# ProDoc_Schematic1_2026-01-19.net
KiCad netlist of a schematic drawn in EasyEDA Pro
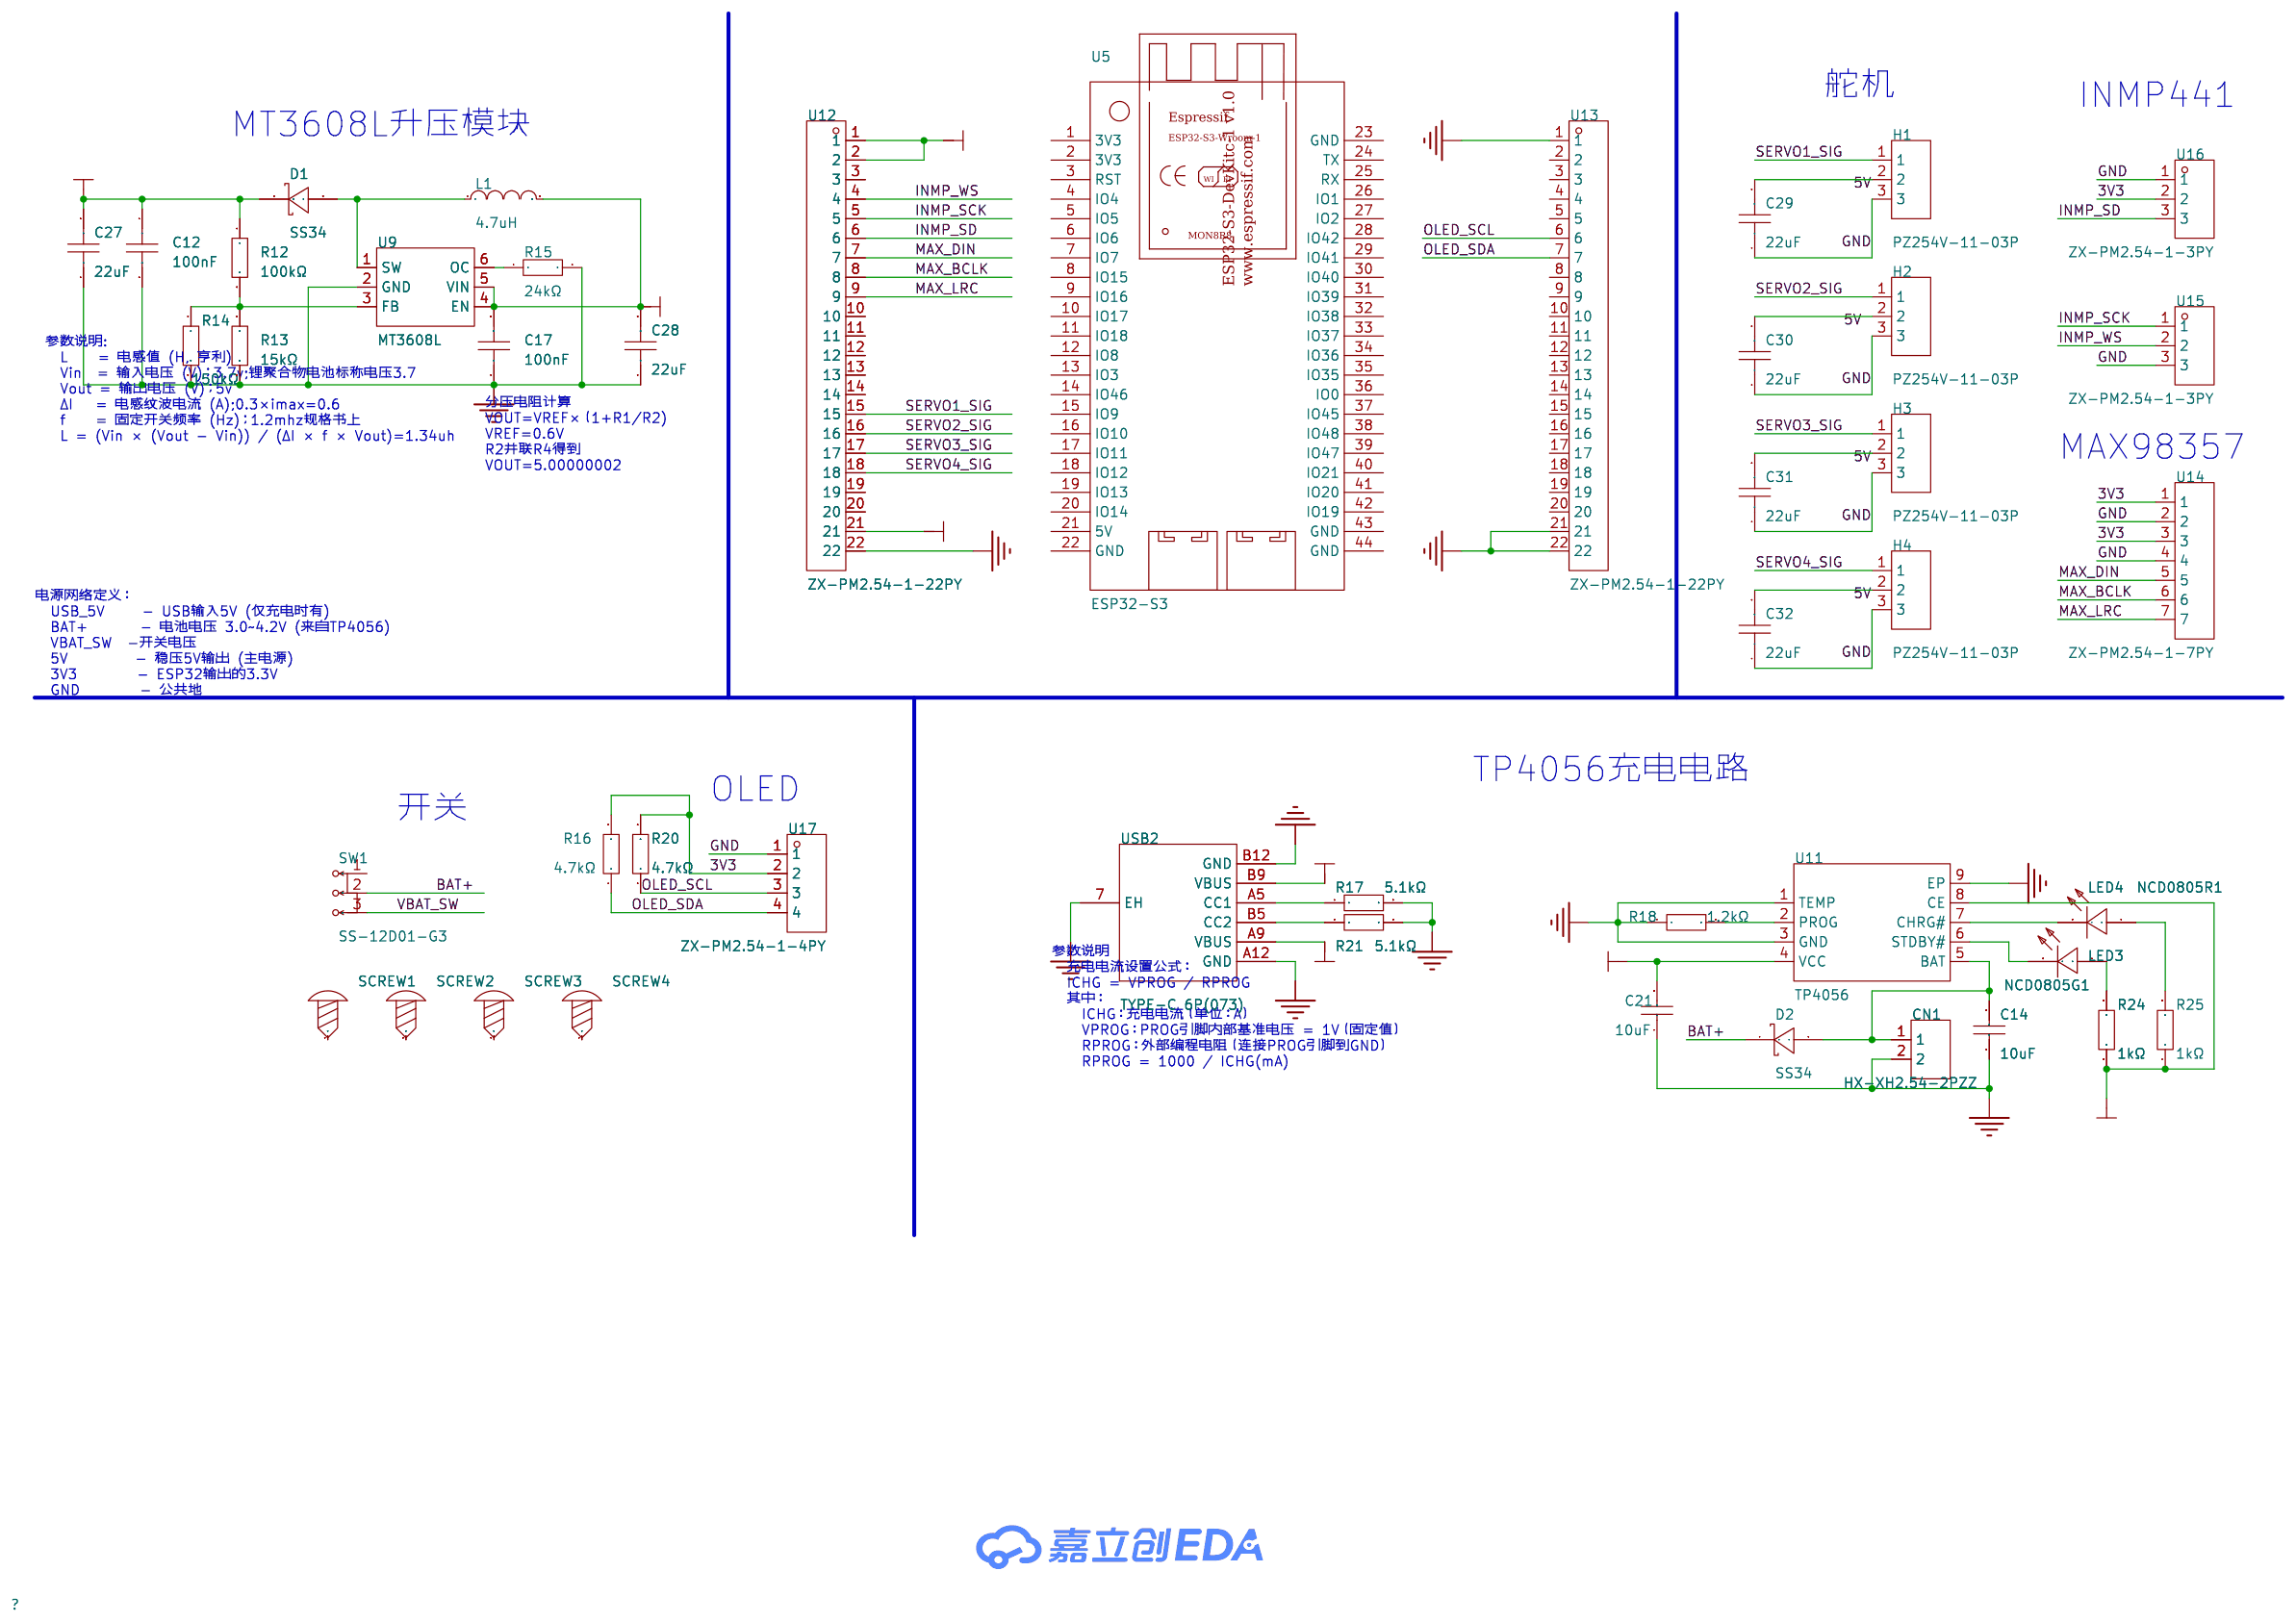
[diagram p0: schematic sheet]

(export (version "E")
  (design (tool "Eeschema 10.0.6"))
  (components
    (comp (ref "C12")
      (value "100nF")
      (footprint "easyedapro:C0805")
      (description "容值:100nF;精度:±10%;额定电压:50V;温度系数:X7R;")
      (fields
        (field (name "Manufacturer Part") "CC0805KRX7R9BB104")
        (field (name "Manufacturer") "YAGEO(国巨)")
      )
      (libsource (lib "easyedapro") (part "CC0805KRX7R9BB104"))
    )
    (comp (ref "C14")
      (value "10uF")
      (footprint "easyedapro:C0805")
      (description "容值:10uF;精度:±10%;额定电压:10V;温度系数:X5R;")
      (fields
        (field (name "Manufacturer Part") "CL21A106KPFNNNE")
        (field (name "Manufacturer") "SAMSUNG(三星)")
      )
      (libsource (lib "easyedapro") (part "CL21A106KPFNNNE"))
    )
    (comp (ref "C17")
      (value "100nF")
      (footprint "easyedapro:C0805")
      (description "容值:100nF;精度:±10%;额定电压:50V;温度系数:X7R;")
      (fields
        (field (name "Manufacturer Part") "CC0805KRX7R9BB104")
        (field (name "Manufacturer") "YAGEO(国巨)")
      )
      (libsource (lib "easyedapro") (part "CC0805KRX7R9BB104"))
    )
    (comp (ref "C21")
      (value "10uF")
      (footprint "easyedapro:C0805")
      (description "容值:10uF;精度:±10%;额定电压:10V;温度系数:X5R;")
      (fields
        (field (name "Manufacturer Part") "CL21A106KPFNNNE")
        (field (name "Manufacturer") "SAMSUNG(三星)")
      )
      (libsource (lib "easyedapro") (part "CL21A106KPFNNNE"))
    )
    (comp (ref "C27")
      (value "22uF")
      (footprint "easyedapro:C0805")
      (description "容值:22uF;精度:±20%;额定电压:25V;温度系数:X5R;")
      (fields
        (field (name "Manufacturer Part") "CL21A226MAQNNNE")
        (field (name "Manufacturer") "SAMSUNG(三星)")
      )
      (libsource (lib "easyedapro") (part "CL21A226MAQNNNE"))
    )
    (comp (ref "C28")
      (value "22uF")
      (footprint "easyedapro:C0805")
      (description "容值:22uF;精度:±20%;额定电压:25V;温度系数:X5R;")
      (fields
        (field (name "Manufacturer Part") "CL21A226MAQNNNE")
        (field (name "Manufacturer") "SAMSUNG(三星)")
      )
      (libsource (lib "easyedapro") (part "CL21A226MAQNNNE"))
    )
    (comp (ref "C29")
      (value "22uF")
      (footprint "easyedapro:C0805")
      (description "容值:22uF;精度:±20%;额定电压:25V;温度系数:X5R;")
      (fields
        (field (name "Manufacturer Part") "CL21A226MAQNNNE")
        (field (name "Manufacturer") "SAMSUNG(三星)")
      )
      (libsource (lib "easyedapro") (part "CL21A226MAQNNNE"))
    )
    (comp (ref "C30")
      (value "22uF")
      (footprint "easyedapro:C0805")
      (description "容值:22uF;精度:±20%;额定电压:25V;温度系数:X5R;")
      (fields
        (field (name "Manufacturer Part") "CL21A226MAQNNNE")
        (field (name "Manufacturer") "SAMSUNG(三星)")
      )
      (libsource (lib "easyedapro") (part "CL21A226MAQNNNE"))
    )
    (comp (ref "C31")
      (value "22uF")
      (footprint "easyedapro:C0805")
      (description "容值:22uF;精度:±20%;额定电压:25V;温度系数:X5R;")
      (fields
        (field (name "Manufacturer Part") "CL21A226MAQNNNE")
        (field (name "Manufacturer") "SAMSUNG(三星)")
      )
      (libsource (lib "easyedapro") (part "CL21A226MAQNNNE"))
    )
    (comp (ref "C32")
      (value "22uF")
      (footprint "easyedapro:C0805")
      (description "容值:22uF;精度:±20%;额定电压:25V;温度系数:X5R;")
      (fields
        (field (name "Manufacturer Part") "CL21A226MAQNNNE")
        (field (name "Manufacturer") "SAMSUNG(三星)")
      )
      (libsource (lib "easyedapro") (part "CL21A226MAQNNNE"))
    )
    (comp (ref "CN1")
      (value "HX-XH2.54-2PZZ")
      (footprint "easyedapro:CONN-TH_2P-P2.50_HX-2.54MM-2P-ZZ-MS")
      (fields (field (name "Manufacturer") "hanxia(韩下)"))
      (libsource (lib "easyedapro") (part "HX-XH2.54-2PZZ"))
    )
    (comp (ref "D1")
      (value "SS34")
      (footprint "easyedapro:SMA_L4.3-W2.6-LS5.2-RD")
      (description "二极管配置:独立式;正向压降(Vf):550mV@3A;直流反向耐压(Vr):40V;整流电流:3A;")
      (fields (field (name "Manufacturer") "MDD(辰达半导体)"))
      (libsource (lib "easyedapro") (part "SS34_C8678"))
    )
    (comp (ref "D2")
      (value "SS34")
      (footprint "easyedapro:SMA_L4.3-W2.6-LS5.2-RD")
      (description "二极管配置:独立式;正向压降(Vf):550mV@3A;直流反向耐压(Vr):40V;整流电流:3A;")
      (fields (field (name "Manufacturer") "MDD(辰达半导体)"))
      (libsource (lib "easyedapro") (part "SS34_C8678"))
    )
    (comp (ref "H1")
      (value "PZ254V-11-03P")
      (footprint "easyedapro:HDR-TH_3P-P2.54-V-M")
      (fields (field (name "Manufacturer") "XFCN(兴飞)"))
      (libsource (lib "easyedapro") (part "PZ254V-11-03P_C2937625"))
    )
    (comp (ref "H2")
      (value "PZ254V-11-03P")
      (footprint "easyedapro:HDR-TH_3P-P2.54-V-M")
      (fields (field (name "Manufacturer") "XFCN(兴飞)"))
      (libsource (lib "easyedapro") (part "PZ254V-11-03P_C2937625"))
    )
    (comp (ref "H3")
      (value "PZ254V-11-03P")
      (footprint "easyedapro:HDR-TH_3P-P2.54-V-M")
      (fields (field (name "Manufacturer") "XFCN(兴飞)"))
      (libsource (lib "easyedapro") (part "PZ254V-11-03P_C2937625"))
    )
    (comp (ref "H4")
      (value "PZ254V-11-03P")
      (footprint "easyedapro:HDR-TH_3P-P2.54-V-M")
      (fields (field (name "Manufacturer") "XFCN(兴飞)"))
      (libsource (lib "easyedapro") (part "PZ254V-11-03P_C2937625"))
    )
    (comp (ref "L1")
      (value "4.7uH")
      (footprint "easyedapro:IND-SMD_L4.4-W4.2")
      (description "电感值:4.7uH;精度:±20%;额定电流:2.8A;饱和电流(Isat):3A;类型:一体成型电感;")
      (fields (field (name "Manufacturer Part") "FXL0420-4R7-M") (field (name "Manufacturer") "cjiang(长江微电)"))
      (libsource (lib "easyedapro") (part "FXL0420-4R7-M"))
    )
    (comp (ref "LED3")
      (value "NCD0805G1")
      (footprint "easyedapro:LED0805-R-RD")
      (fields (field (name "Manufacturer") "国星光电"))
      (libsource (lib "easyedapro") (part "FC-2012UGK-520D5"))
    )
    (comp (ref "LED4")
      (value "NCD0805R1")
      (footprint "easyedapro:LED0805-R-RD")
      (fields (field (name "Manufacturer") "国星光电"))
      (libsource (lib "easyedapro") (part "FC-2012HRK-620D"))
    )
    (comp (ref "R12")
      (value "100kΩ")
      (footprint "easyedapro:R0805")
      (description "电阻类型:厚膜电阻;阻值:100kΩ;精度:±1%;功率:125mW;工作电压:150V;温度系数:±100ppm/°C;")
      (fields
        (field (name "Manufacturer Part") "0805W8F1003T5E")
        (field (name "Manufacturer") "UNI-ROYAL(厚声)")
      )
      (libsource (lib "easyedapro") (part "0805W8F1003T5E_C149504"))
    )
    (comp (ref "R13")
      (value "15kΩ")
      (footprint "easyedapro:R0805")
      (description "电阻类型:厚膜电阻;阻值:15kΩ;精度:±1%;功率:125mW;工作电压:150V;温度系数:±100ppm/°C;")
      (fields
        (field (name "Manufacturer Part") "0805W8F1502T5E")
        (field (name "Manufacturer") "UNI-ROYAL(厚声)")
      )
      (libsource (lib "easyedapro") (part "0805W8F1502T5E"))
    )
    (comp (ref "R14")
      (value "150kΩ")
      (footprint "easyedapro:R0805")
      (description "电阻类型:厚膜电阻;阻值:150kΩ;精度:±1%;功率:125mW;最大工作电压:150V;温度系数:±100ppm/°C;")
      (fields
        (field (name "Manufacturer Part") "0805W8F1503T5E")
        (field (name "Manufacturer") "UNI-ROYAL(厚声)")
      )
      (libsource (lib "easyedapro") (part "0805W8F1503T5E"))
    )
    (comp (ref "R15")
      (value "24kΩ")
      (footprint "easyedapro:R0805")
      (description "电阻类型:厚膜电阻;阻值:24kΩ;精度:±1%;功率:125mW;工作电压:150V;温度系数:±100ppm/°C;")
      (fields
        (field (name "Manufacturer Part") "0805W8F2402T5E")
        (field (name "Manufacturer") "UNI-ROYAL(厚声)")
      )
      (libsource (lib "easyedapro") (part "0805W8F2402T5E"))
    )
    (comp (ref "R16")
      (value "4.7kΩ")
      (footprint "easyedapro:R0805")
      (description "电阻类型:厚膜电阻;阻值:4.7kΩ;精度:±1%;功率:125mW;最大工作电压:150V;温度系数:±100ppm/°C;")
      (fields
        (field (name "Manufacturer Part") "0805W8F4701T5E")
        (field (name "Manufacturer") "UNI-ROYAL(厚声)")
      )
      (libsource (lib "easyedapro") (part "0805W8F4701T5E"))
    )
    (comp (ref "R17")
      (value "5.1kΩ")
      (footprint "easyedapro:R0805")
      (description "电阻类型:厚膜电阻;阻值:5.1kΩ;精度:±1%;功率:125mW;工作电压:150V;温度系数:±100ppm/°C;")
      (fields
        (field (name "Manufacturer Part") "0805W8F5101T5E")
        (field (name "Manufacturer") "UNI-ROYAL(厚声)")
      )
      (libsource (lib "easyedapro") (part "0805W8F5101T5E"))
    )
    (comp (ref "R18")
      (value "1.2kΩ")
      (footprint "easyedapro:R0805")
      (description "电阻类型:厚膜电阻;阻值:1.2kΩ;精度:±1%;功率:125mW;工作电压:150V;温度系数:±100ppm/°C;")
      (fields
        (field (name "Manufacturer Part") "0805W8F1201T5E")
        (field (name "Manufacturer") "UNI-ROYAL(厚声)")
      )
      (libsource (lib "easyedapro") (part "0805W8F1201T5E"))
    )
    (comp (ref "R20")
      (value "4.7kΩ")
      (footprint "easyedapro:R0805")
      (description "电阻类型:厚膜电阻;阻值:4.7kΩ;精度:±1%;功率:125mW;最大工作电压:150V;温度系数:±100ppm/°C;")
      (fields
        (field (name "Manufacturer Part") "0805W8F4701T5E")
        (field (name "Manufacturer") "UNI-ROYAL(厚声)")
      )
      (libsource (lib "easyedapro") (part "0805W8F4701T5E"))
    )
    (comp (ref "R21")
      (value "5.1kΩ")
      (footprint "easyedapro:R0805")
      (description "电阻类型:厚膜电阻;阻值:5.1kΩ;精度:±1%;功率:125mW;工作电压:150V;温度系数:±100ppm/°C;")
      (fields
        (field (name "Manufacturer Part") "0805W8F5101T5E")
        (field (name "Manufacturer") "UNI-ROYAL(厚声)")
      )
      (libsource (lib "easyedapro") (part "0805W8F5101T5E"))
    )
    (comp (ref "R24")
      (value "1kΩ")
      (footprint "easyedapro:R0805")
      (description "电阻类型:厚膜电阻;阻值:1kΩ;精度:±1%;功率:125mW;最大工作电压:150V;温度系数:±100ppm/°C;")
      (fields
        (field (name "Manufacturer Part") "0805W8F1001T5E")
        (field (name "Manufacturer") "UNI-ROYAL(厚声)")
      )
      (libsource (lib "easyedapro") (part "0805W8F1001T5E"))
    )
    (comp (ref "R25")
      (value "1kΩ")
      (footprint "easyedapro:R0805")
      (description "电阻类型:厚膜电阻;阻值:1kΩ;精度:±1%;功率:125mW;最大工作电压:150V;温度系数:±100ppm/°C;")
      (fields
        (field (name "Manufacturer Part") "0805W8F1001T5E")
        (field (name "Manufacturer") "UNI-ROYAL(厚声)")
      )
      (libsource (lib "easyedapro") (part "0805W8F1001T5E"))
    )
    (comp (ref "SCREW1")
      (value "~")
      (footprint "easyedapro:M3螺丝")
      (libsource (lib "easyedapro") (part "螺丝孔"))
    )
    (comp (ref "SCREW2")
      (value "~")
      (footprint "easyedapro:M3螺丝")
      (libsource (lib "easyedapro") (part "螺丝孔"))
    )
    (comp (ref "SCREW3")
      (value "~")
      (footprint "easyedapro:M3螺丝")
      (libsource (lib "easyedapro") (part "螺丝孔"))
    )
    (comp (ref "SCREW4")
      (value "~")
      (footprint "easyedapro:M3螺丝")
      (libsource (lib "easyedapro") (part "螺丝孔"))
    )
    (comp (ref "SW1")
      (value "SS-12D01-G3")
      (footprint "easyedapro:SW-TH_SS-12D01-GX")
      (description "电路结构:单刀双掷;额定电流:300mA;额定电压:50V;工作寿命:1万次;")
      (fields (field (name "Manufacturer") "USAKRO(美韩)"))
      (libsource (lib "easyedapro") (part "SS-12D01-G3"))
    )
    (comp (ref "U5")
      (value "ESP32-S3")
      (footprint "easyedapro:ESP32-S3-DevKitC-1")
      (description "ESP32-S3-DEVKITC-1-乐鑫官方开发板")
      (fields (field (name "Manufacturer") "乐鑫科技"))
      (libsource (lib "easyedapro") (part "ESP32-S3-DEVKITC-1"))
    )
    (comp (ref "U9")
      (value "MT3608L")
      (footprint "easyedapro:SOT-23-6_L2.9-W1.6-P0.95-LS2.8-BL_3")
      (description "功能类型:升压型;工作电压:2.2V~16V;输出电压:-;输出电流:2.5A;输出类型:可调;")
      (fields (field (name "Manufacturer") "西安航天民芯"))
      (libsource (lib "easyedapro") (part "MT3608L"))
    )
    (comp (ref "U11")
      (value "TP4056")
      (footprint "easyedapro:ESOP-8_L4.9-W3.9-P1.27-LS6.0-BL-EP")
      (description "工作电压:3.7V~6.5V;最大充电电流:1A;电池类型:锂离子;电池节数:1;")
      (fields (field (name "Manufacturer") "UMW(友台半导体)"))
      (libsource (lib "easyedapro") (part "TP4056_C725790"))
    )
    (comp (ref "U12")
      (value "ZX-PM2.54-1-22PY")
      (footprint "easyedapro:HDR-TH_22P-P2.54-V-F")
      (fields (field (name "Manufacturer") "Megastar(兆星)"))
      (libsource (lib "easyedapro") (part "ZX-PM2.54-1-22PY"))
    )
    (comp (ref "U13")
      (value "ZX-PM2.54-1-22PY")
      (footprint "easyedapro:HDR-TH_22P-P2.54-V-F")
      (fields (field (name "Manufacturer") "Megastar(兆星)"))
      (libsource (lib "easyedapro") (part "ZX-PM2.54-1-22PY"))
    )
    (comp (ref "U14")
      (value "ZX-PM2.54-1-7PY")
      (footprint "easyedapro:HDR-TH_7P-P2.54-V-F")
      (fields (field (name "Manufacturer") "Megastar(兆星)"))
      (libsource (lib "easyedapro") (part "ZX-PM2.54-1-7PY"))
    )
    (comp (ref "U15")
      (value "ZX-PM2.54-1-3PY")
      (footprint "easyedapro:HDR-TH_3P-P2.54-V-F")
      (fields (field (name "Manufacturer") "Megastar(兆星)"))
      (libsource (lib "easyedapro") (part "ZX-PM2.54-1-3PY"))
    )
    (comp (ref "U16")
      (value "ZX-PM2.54-1-3PY")
      (footprint "easyedapro:HDR-TH_3P-P2.54-V-F")
      (fields (field (name "Manufacturer") "Megastar(兆星)"))
      (libsource (lib "easyedapro") (part "ZX-PM2.54-1-3PY"))
    )
    (comp (ref "U17")
      (value "ZX-PM2.54-1-4PY")
      (footprint "easyedapro:HDR-TH_4P-P2.54-V-F")
      (fields (field (name "Manufacturer") "Megastar(兆星)"))
      (libsource (lib "easyedapro") (part "ZX-PM2.54-1-4PY"))
    )
    (comp (ref "USB2")
      (value "TYPE-C 6P(073)")
      (footprint "easyedapro:TYPE-C-SMD_TYPE-C-6P-073")
      (description "连接器类型:Type-C;标准:USB 3.1;公母:母;安装方式:卧贴;触点数量:6P;端口数量:1;额定电流 - 电源:3A;工作温度范围:-25°C~+85°C;")
      (fields (field (name "Manufacturer") "SHOU HAN(首韩)"))
      (libsource (lib "easyedapro") (part "TYPE-C 6P(073)"))
    )
  )
  (nets
    (net (code "1") (name "/BAT+") (class "Default")
      (node (ref "D2") (pin "1") (pinfunction "K_1") (pintype "unspecified"))
      (node (ref "SW1") (pin "2") (pinfunction "2_2") (pintype "unspecified"))
    )
    (net (code "2") (name "/INMP_SCK") (class "Default")
      (node (ref "U12") (pin "5") (pinfunction "5_5") (pintype "unspecified"))
      (node (ref "U15") (pin "1") (pinfunction "1_1") (pintype "unspecified"))
    )
    (net (code "3") (name "/INMP_SD") (class "Default")
      (node (ref "U12") (pin "6") (pinfunction "6_6") (pintype "unspecified"))
      (node (ref "U16") (pin "3") (pinfunction "3_3") (pintype "unspecified"))
    )
    (net (code "4") (name "/INMP_WS") (class "Default")
      (node (ref "U12") (pin "4") (pinfunction "4_4") (pintype "unspecified"))
      (node (ref "U15") (pin "2") (pinfunction "2_2") (pintype "unspecified"))
    )
    (net (code "5") (name "/MAX_BCLK") (class "Default")
      (node (ref "U12") (pin "8") (pinfunction "8_8") (pintype "unspecified"))
      (node (ref "U14") (pin "6") (pinfunction "6_6") (pintype "unspecified"))
    )
    (net (code "6") (name "/MAX_DIN") (class "Default")
      (node (ref "U12") (pin "7") (pinfunction "7_7") (pintype "unspecified"))
      (node (ref "U14") (pin "5") (pinfunction "5_5") (pintype "unspecified"))
    )
    (net (code "7") (name "/MAX_LRC") (class "Default")
      (node (ref "U12") (pin "9") (pinfunction "9_9") (pintype "unspecified"))
      (node (ref "U14") (pin "7") (pinfunction "7_7") (pintype "unspecified"))
    )
    (net (code "8") (name "/OLED_SCL") (class "Default")
      (node (ref "R20") (pin "1") (pinfunction "1_1") (pintype "input"))
      (node (ref "U13") (pin "6") (pinfunction "6_6") (pintype "unspecified"))
      (node (ref "U17") (pin "3") (pinfunction "3_3") (pintype "unspecified"))
    )
    (net (code "9") (name "/OLED_SDA") (class "Default")
      (node (ref "R16") (pin "1") (pinfunction "1_1") (pintype "input"))
      (node (ref "U13") (pin "7") (pinfunction "7_7") (pintype "unspecified"))
      (node (ref "U17") (pin "4") (pinfunction "4_4") (pintype "unspecified"))
    )
    (net (code "10") (name "/SERVO1_SIG") (class "Default")
      (node (ref "H1") (pin "1") (pinfunction "1_1") (pintype "unspecified"))
      (node (ref "U12") (pin "15") (pinfunction "15_15") (pintype "unspecified"))
    )
    (net (code "11") (name "/SERVO2_SIG") (class "Default")
      (node (ref "H2") (pin "1") (pinfunction "1_1") (pintype "unspecified"))
      (node (ref "U12") (pin "16") (pinfunction "16_16") (pintype "unspecified"))
    )
    (net (code "12") (name "/SERVO3_SIG") (class "Default")
      (node (ref "H3") (pin "1") (pinfunction "1_1") (pintype "unspecified"))
      (node (ref "U12") (pin "17") (pinfunction "17_17") (pintype "unspecified"))
    )
    (net (code "13") (name "/SERVO4_SIG") (class "Default")
      (node (ref "H4") (pin "1") (pinfunction "1_1") (pintype "unspecified"))
      (node (ref "U12") (pin "18") (pinfunction "18_18") (pintype "unspecified"))
    )
    (net (code "14") (name "3V3") (class "Default")
      (node (ref "R16") (pin "2") (pinfunction "2_2") (pintype "input"))
      (node (ref "R20") (pin "2") (pinfunction "2_2") (pintype "input"))
      (node (ref "U12") (pin "1") (pinfunction "1_1") (pintype "unspecified"))
      (node (ref "U12") (pin "2") (pinfunction "2_2") (pintype "unspecified"))
      (node (ref "U14") (pin "1") (pinfunction "1_1") (pintype "unspecified"))
      (node (ref "U14") (pin "3") (pinfunction "3_3") (pintype "unspecified"))
      (node (ref "U16") (pin "2") (pinfunction "2_2") (pintype "unspecified"))
      (node (ref "U17") (pin "2") (pinfunction "2_2") (pintype "unspecified"))
    )
    (net (code "15") (name "5V") (class "Default")
      (node (ref "C12") (pin "1") (pinfunction "1_1") (pintype "unspecified"))
      (node (ref "C27") (pin "2") (pinfunction "2_2") (pintype "unspecified"))
      (node (ref "C29") (pin "2") (pinfunction "2_2") (pintype "unspecified"))
      (node (ref "C30") (pin "2") (pinfunction "2_2") (pintype "unspecified"))
      (node (ref "C31") (pin "2") (pinfunction "2_2") (pintype "unspecified"))
      (node (ref "C32") (pin "2") (pinfunction "2_2") (pintype "unspecified"))
      (node (ref "D1") (pin "1") (pinfunction "K_1") (pintype "unspecified"))
      (node (ref "H1") (pin "2") (pinfunction "2_2") (pintype "unspecified"))
      (node (ref "H2") (pin "2") (pinfunction "2_2") (pintype "unspecified"))
      (node (ref "H3") (pin "2") (pinfunction "2_2") (pintype "unspecified"))
      (node (ref "H4") (pin "2") (pinfunction "2_2") (pintype "unspecified"))
      (node (ref "R12") (pin "1") (pinfunction "1_1") (pintype "unspecified"))
      (node (ref "U12") (pin "21") (pinfunction "21_21") (pintype "unspecified"))
    )
    (net (code "16") (name "GND") (class "Default")
      (node (ref "C12") (pin "2") (pinfunction "2_2") (pintype "unspecified"))
      (node (ref "C14") (pin "1") (pinfunction "1_1") (pintype "input"))
      (node (ref "C17") (pin "1") (pinfunction "1_1") (pintype "unspecified"))
      (node (ref "C21") (pin "1") (pinfunction "1_1") (pintype "input"))
      (node (ref "C27") (pin "1") (pinfunction "1_1") (pintype "unspecified"))
      (node (ref "C28") (pin "1") (pinfunction "1_1") (pintype "unspecified"))
      (node (ref "C29") (pin "1") (pinfunction "1_1") (pintype "unspecified"))
      (node (ref "C30") (pin "1") (pinfunction "1_1") (pintype "unspecified"))
      (node (ref "C31") (pin "1") (pinfunction "1_1") (pintype "unspecified"))
      (node (ref "C32") (pin "1") (pinfunction "1_1") (pintype "unspecified"))
      (node (ref "CN1") (pin "2") (pinfunction "2_2") (pintype "unspecified"))
      (node (ref "H1") (pin "3") (pinfunction "3_3") (pintype "unspecified"))
      (node (ref "H2") (pin "3") (pinfunction "3_3") (pintype "unspecified"))
      (node (ref "H3") (pin "3") (pinfunction "3_3") (pintype "unspecified"))
      (node (ref "H4") (pin "3") (pinfunction "3_3") (pintype "unspecified"))
      (node (ref "R13") (pin "2") (pinfunction "2_2") (pintype "input"))
      (node (ref "R14") (pin "2") (pinfunction "2_2") (pintype "input"))
      (node (ref "R15") (pin "2") (pinfunction "2_2") (pintype "input"))
      (node (ref "R17") (pin "2") (pinfunction "2_2") (pintype "input"))
      (node (ref "R18") (pin "1") (pinfunction "1_1") (pintype "input"))
      (node (ref "R21") (pin "2") (pinfunction "2_2") (pintype "input"))
      (node (ref "U11") (pin "1") (pinfunction "TEMP_1") (pintype "unspecified"))
      (node (ref "U11") (pin "3") (pinfunction "GND_3") (pintype "unspecified"))
      (node (ref "U11") (pin "9") (pinfunction "EP_9") (pintype "unspecified"))
      (node (ref "U12") (pin "22") (pinfunction "22_22") (pintype "unspecified"))
      (node (ref "U13") (pin "1") (pinfunction "1_1") (pintype "unspecified"))
      (node (ref "U13") (pin "21") (pinfunction "21_21") (pintype "unspecified"))
      (node (ref "U13") (pin "22") (pinfunction "22_22") (pintype "unspecified"))
      (node (ref "U14") (pin "2") (pinfunction "2_2") (pintype "unspecified"))
      (node (ref "U14") (pin "4") (pinfunction "4_4") (pintype "unspecified"))
      (node (ref "U15") (pin "3") (pinfunction "3_3") (pintype "unspecified"))
      (node (ref "U16") (pin "1") (pinfunction "1_1") (pintype "unspecified"))
      (node (ref "U17") (pin "1") (pinfunction "1_1") (pintype "unspecified"))
      (node (ref "U9") (pin "2") (pinfunction "GND_2") (pintype "unspecified"))
      (node (ref "USB2") (pin "7") (pinfunction "EH_7") (pintype "unspecified"))
      (node (ref "USB2") (pin "A12") (pinfunction "GND_A12") (pintype "unspecified"))
      (node (ref "USB2") (pin "B12") (pinfunction "GND_B12") (pintype "unspecified"))
    )
    (net (code "17") (name "Net-(D1-A)") (class "Default")
      (node (ref "D1") (pin "2") (pinfunction "A_2") (pintype "unspecified"))
      (node (ref "L1") (pin "1") (pinfunction "1_1") (pintype "unspecified"))
      (node (ref "U9") (pin "1") (pinfunction "SW_1") (pintype "unspecified"))
    )
    (net (code "18") (name "Net-(D2-A)") (class "Default")
      (node (ref "C14") (pin "2") (pinfunction "2_2") (pintype "input"))
      (node (ref "CN1") (pin "1") (pinfunction "1_1") (pintype "unspecified"))
      (node (ref "D2") (pin "2") (pinfunction "A_2") (pintype "unspecified"))
      (node (ref "U11") (pin "5") (pinfunction "BAT_5") (pintype "unspecified"))
    )
    (net (code "19") (name "Net-(LED3-A)") (class "Default")
      (node (ref "LED3") (pin "1") (pinfunction "A_1") (pintype "unspecified"))
      (node (ref "R24") (pin "2") (pinfunction "2_2") (pintype "input"))
    )
    (net (code "20") (name "Net-(LED3-K)") (class "Default")
      (node (ref "LED3") (pin "2") (pinfunction "K_2") (pintype "unspecified"))
      (node (ref "U11") (pin "6") (pinfunction "STDBY#_6") (pintype "unspecified"))
    )
    (net (code "21") (name "Net-(LED4-+)") (class "Default")
      (node (ref "LED4") (pin "1") (pinfunction "+_1") (pintype "unspecified"))
      (node (ref "R25") (pin "2") (pinfunction "2_2") (pintype "input"))
    )
    (net (code "22") (name "Net-(LED4--)") (class "Default")
      (node (ref "LED4") (pin "2") (pinfunction "-_2") (pintype "unspecified"))
      (node (ref "U11") (pin "7") (pinfunction "CHRG#_7") (pintype "unspecified"))
    )
    (net (code "23") (name "Net-(U9-FB)") (class "Default")
      (node (ref "R12") (pin "2") (pinfunction "2_2") (pintype "unspecified"))
      (node (ref "R13") (pin "1") (pinfunction "1_1") (pintype "input"))
      (node (ref "R14") (pin "1") (pinfunction "1_1") (pintype "input"))
      (node (ref "U9") (pin "3") (pinfunction "FB_3") (pintype "unspecified"))
    )
    (net (code "24") (name "Net-(U9-OC)") (class "Default")
      (node (ref "R15") (pin "1") (pinfunction "1_1") (pintype "input"))
      (node (ref "U9") (pin "6") (pinfunction "OC_6") (pintype "unspecified"))
    )
    (net (code "25") (name "Net-(U11-PROG)") (class "Default")
      (node (ref "R18") (pin "2") (pinfunction "2_2") (pintype "input"))
      (node (ref "U11") (pin "2") (pinfunction "PROG_2") (pintype "unspecified"))
    )
    (net (code "26") (name "Net-(USB2-CC1)") (class "Default")
      (node (ref "R17") (pin "1") (pinfunction "1_1") (pintype "input"))
      (node (ref "USB2") (pin "A5") (pinfunction "CC1_A5") (pintype "unspecified"))
    )
    (net (code "27") (name "Net-(USB2-CC2)") (class "Default")
      (node (ref "R21") (pin "1") (pinfunction "1_1") (pintype "input"))
      (node (ref "USB2") (pin "B5") (pinfunction "CC2_B5") (pintype "unspecified"))
    )
    (net (code "28") (name "USB_5V") (class "Default")
      (node (ref "C21") (pin "2") (pinfunction "2_2") (pintype "input"))
      (node (ref "R24") (pin "1") (pinfunction "1_1") (pintype "input"))
      (node (ref "R25") (pin "1") (pinfunction "1_1") (pintype "input"))
      (node (ref "U11") (pin "4") (pinfunction "VCC_4") (pintype "unspecified"))
      (node (ref "U11") (pin "8") (pinfunction "CE_8") (pintype "unspecified"))
      (node (ref "USB2") (pin "A9") (pinfunction "VBUS_A9") (pintype "unspecified"))
      (node (ref "USB2") (pin "B9") (pinfunction "VBUS_B9") (pintype "unspecified"))
    )
    (net (code "29") (name "VBAT_SW") (class "Default")
      (node (ref "C17") (pin "2") (pinfunction "2_2") (pintype "unspecified"))
      (node (ref "C28") (pin "2") (pinfunction "2_2") (pintype "unspecified"))
      (node (ref "L1") (pin "2") (pinfunction "2_2") (pintype "unspecified"))
      (node (ref "SW1") (pin "3") (pinfunction "3_3") (pintype "unspecified"))
      (node (ref "U9") (pin "4") (pinfunction "EN_4") (pintype "unspecified"))
      (node (ref "U9") (pin "5") (pinfunction "VIN_5") (pintype "unspecified"))
    )
    (net (code "30") (name "unconnected-(SCREW1-Pad1)") (class "Default")
      (node (ref "SCREW1") (pin "1") (pinfunction "1_1") (pintype "input"))
    )
    (net (code "31") (name "unconnected-(SCREW2-Pad1)") (class "Default")
      (node (ref "SCREW2") (pin "1") (pinfunction "1_1") (pintype "input"))
    )
    (net (code "32") (name "unconnected-(SCREW3-Pad1)") (class "Default")
      (node (ref "SCREW3") (pin "1") (pinfunction "1_1") (pintype "input"))
    )
    (net (code "33") (name "unconnected-(SCREW4-Pad1)") (class "Default")
      (node (ref "SCREW4") (pin "1") (pinfunction "1_1") (pintype "input"))
    )
    (net (code "34") (name "unconnected-(SW1-Pad1)") (class "Default")
      (node (ref "SW1") (pin "1") (pinfunction "1_1") (pintype "unspecified"))
    )
    (net (code "35") (name "unconnected-(U5-3V3-Pad1)") (class "Default")
      (node (ref "U5") (pin "1") (pinfunction "3V3_1") (pintype "input"))
    )
    (net (code "36") (name "unconnected-(U5-3V3-Pad2)") (class "Default")
      (node (ref "U5") (pin "2") (pinfunction "3V3_2") (pintype "input"))
    )
    (net (code "37") (name "unconnected-(U5-5V-Pad21)") (class "Default")
      (node (ref "U5") (pin "21") (pinfunction "5V_21") (pintype "input"))
    )
    (net (code "38") (name "unconnected-(U5-GND-Pad22)") (class "Default")
      (node (ref "U5") (pin "22") (pinfunction "GND_22") (pintype "input"))
    )
    (net (code "39") (name "unconnected-(U5-GND-Pad23)") (class "Default")
      (node (ref "U5") (pin "23") (pinfunction "GND_23") (pintype "input"))
    )
    (net (code "40") (name "unconnected-(U5-GND-Pad43)") (class "Default")
      (node (ref "U5") (pin "43") (pinfunction "GND_43") (pintype "input"))
    )
    (net (code "41") (name "unconnected-(U5-GND-Pad44)") (class "Default")
      (node (ref "U5") (pin "44") (pinfunction "GND_44") (pintype "input"))
    )
    (net (code "42") (name "unconnected-(U5-IO0-Pad36)") (class "Default")
      (node (ref "U5") (pin "36") (pinfunction "IO0_36") (pintype "input"))
    )
    (net (code "43") (name "unconnected-(U5-IO1-Pad26)") (class "Default")
      (node (ref "U5") (pin "26") (pinfunction "IO1_26") (pintype "input"))
    )
    (net (code "44") (name "unconnected-(U5-IO2-Pad27)") (class "Default")
      (node (ref "U5") (pin "27") (pinfunction "IO2_27") (pintype "input"))
    )
    (net (code "45") (name "unconnected-(U5-IO3-Pad13)") (class "Default")
      (node (ref "U5") (pin "13") (pinfunction "IO3_13") (pintype "input"))
    )
    (net (code "46") (name "unconnected-(U5-IO4-Pad4)") (class "Default")
      (node (ref "U5") (pin "4") (pinfunction "IO4_4") (pintype "input"))
    )
    (net (code "47") (name "unconnected-(U5-IO5-Pad5)") (class "Default")
      (node (ref "U5") (pin "5") (pinfunction "IO5_5") (pintype "input"))
    )
    (net (code "48") (name "unconnected-(U5-IO6-Pad6)") (class "Default")
      (node (ref "U5") (pin "6") (pinfunction "IO6_6") (pintype "input"))
    )
    (net (code "49") (name "unconnected-(U5-IO7-Pad7)") (class "Default")
      (node (ref "U5") (pin "7") (pinfunction "IO7_7") (pintype "input"))
    )
    (net (code "50") (name "unconnected-(U5-IO8-Pad12)") (class "Default")
      (node (ref "U5") (pin "12") (pinfunction "IO8_12") (pintype "input"))
    )
    (net (code "51") (name "unconnected-(U5-IO9-Pad15)") (class "Default")
      (node (ref "U5") (pin "15") (pinfunction "IO9_15") (pintype "input"))
    )
    (net (code "52") (name "unconnected-(U5-IO10-Pad16)") (class "Default")
      (node (ref "U5") (pin "16") (pinfunction "IO10_16") (pintype "input"))
    )
    (net (code "53") (name "unconnected-(U5-IO11-Pad17)") (class "Default")
      (node (ref "U5") (pin "17") (pinfunction "IO11_17") (pintype "input"))
    )
    (net (code "54") (name "unconnected-(U5-IO12-Pad18)") (class "Default")
      (node (ref "U5") (pin "18") (pinfunction "IO12_18") (pintype "input"))
    )
    (net (code "55") (name "unconnected-(U5-IO13-Pad19)") (class "Default")
      (node (ref "U5") (pin "19") (pinfunction "IO13_19") (pintype "input"))
    )
    (net (code "56") (name "unconnected-(U5-IO14-Pad20)") (class "Default")
      (node (ref "U5") (pin "20") (pinfunction "IO14_20") (pintype "input"))
    )
    (net (code "57") (name "unconnected-(U5-IO15-Pad8)") (class "Default")
      (node (ref "U5") (pin "8") (pinfunction "IO15_8") (pintype "input"))
    )
    (net (code "58") (name "unconnected-(U5-IO16-Pad9)") (class "Default")
      (node (ref "U5") (pin "9") (pinfunction "IO16_9") (pintype "input"))
    )
    (net (code "59") (name "unconnected-(U5-IO17-Pad10)") (class "Default")
      (node (ref "U5") (pin "10") (pinfunction "IO17_10") (pintype "input"))
    )
    (net (code "60") (name "unconnected-(U5-IO18-Pad11)") (class "Default")
      (node (ref "U5") (pin "11") (pinfunction "IO18_11") (pintype "input"))
    )
    (net (code "61") (name "unconnected-(U5-IO19-Pad42)") (class "Default")
      (node (ref "U5") (pin "42") (pinfunction "IO19_42") (pintype "input"))
    )
    (net (code "62") (name "unconnected-(U5-IO20-Pad41)") (class "Default")
      (node (ref "U5") (pin "41") (pinfunction "IO20_41") (pintype "input"))
    )
    (net (code "63") (name "unconnected-(U5-IO21-Pad40)") (class "Default")
      (node (ref "U5") (pin "40") (pinfunction "IO21_40") (pintype "input"))
    )
    (net (code "64") (name "unconnected-(U5-IO35-Pad35)") (class "Default")
      (node (ref "U5") (pin "35") (pinfunction "IO35_35") (pintype "input"))
    )
    (net (code "65") (name "unconnected-(U5-IO36-Pad34)") (class "Default")
      (node (ref "U5") (pin "34") (pinfunction "IO36_34") (pintype "input"))
    )
    (net (code "66") (name "unconnected-(U5-IO37-Pad33)") (class "Default")
      (node (ref "U5") (pin "33") (pinfunction "IO37_33") (pintype "input"))
    )
    (net (code "67") (name "unconnected-(U5-IO38-Pad32)") (class "Default")
      (node (ref "U5") (pin "32") (pinfunction "IO38_32") (pintype "input"))
    )
    (net (code "68") (name "unconnected-(U5-IO39-Pad31)") (class "Default")
      (node (ref "U5") (pin "31") (pinfunction "IO39_31") (pintype "input"))
    )
    (net (code "69") (name "unconnected-(U5-IO40-Pad30)") (class "Default")
      (node (ref "U5") (pin "30") (pinfunction "IO40_30") (pintype "input"))
    )
    (net (code "70") (name "unconnected-(U5-IO41-Pad29)") (class "Default")
      (node (ref "U5") (pin "29") (pinfunction "IO41_29") (pintype "input"))
    )
    (net (code "71") (name "unconnected-(U5-IO42-Pad28)") (class "Default")
      (node (ref "U5") (pin "28") (pinfunction "IO42_28") (pintype "input"))
    )
    (net (code "72") (name "unconnected-(U5-IO45-Pad37)") (class "Default")
      (node (ref "U5") (pin "37") (pinfunction "IO45_37") (pintype "input"))
    )
    (net (code "73") (name "unconnected-(U5-IO46-Pad14)") (class "Default")
      (node (ref "U5") (pin "14") (pinfunction "IO46_14") (pintype "input"))
    )
    (net (code "74") (name "unconnected-(U5-IO47-Pad39)") (class "Default")
      (node (ref "U5") (pin "39") (pinfunction "IO47_39") (pintype "input"))
    )
    (net (code "75") (name "unconnected-(U5-IO48-Pad38)") (class "Default")
      (node (ref "U5") (pin "38") (pinfunction "IO48_38") (pintype "input"))
    )
    (net (code "76") (name "unconnected-(U5-RST-Pad3)") (class "Default")
      (node (ref "U5") (pin "3") (pinfunction "RST_3") (pintype "input"))
    )
    (net (code "77") (name "unconnected-(U5-RX-Pad25)") (class "Default")
      (node (ref "U5") (pin "25") (pinfunction "RX_25") (pintype "input"))
    )
    (net (code "78") (name "unconnected-(U5-TX-Pad24)") (class "Default")
      (node (ref "U5") (pin "24") (pinfunction "TX_24") (pintype "input"))
    )
    (net (code "79") (name "unconnected-(U12-Pad3)") (class "Default")
      (node (ref "U12") (pin "3") (pinfunction "3_3") (pintype "unspecified"))
    )
    (net (code "80") (name "unconnected-(U12-Pad10)") (class "Default")
      (node (ref "U12") (pin "10") (pinfunction "10_10") (pintype "unspecified"))
    )
    (net (code "81") (name "unconnected-(U12-Pad11)") (class "Default")
      (node (ref "U12") (pin "11") (pinfunction "11_11") (pintype "unspecified"))
    )
    (net (code "82") (name "unconnected-(U12-Pad12)") (class "Default")
      (node (ref "U12") (pin "12") (pinfunction "12_12") (pintype "unspecified"))
    )
    (net (code "83") (name "unconnected-(U12-Pad13)") (class "Default")
      (node (ref "U12") (pin "13") (pinfunction "13_13") (pintype "unspecified"))
    )
    (net (code "84") (name "unconnected-(U12-Pad14)") (class "Default")
      (node (ref "U12") (pin "14") (pinfunction "14_14") (pintype "unspecified"))
    )
    (net (code "85") (name "unconnected-(U12-Pad19)") (class "Default")
      (node (ref "U12") (pin "19") (pinfunction "19_19") (pintype "unspecified"))
    )
    (net (code "86") (name "unconnected-(U12-Pad20)") (class "Default")
      (node (ref "U12") (pin "20") (pinfunction "20_20") (pintype "unspecified"))
    )
    (net (code "87") (name "unconnected-(U13-Pad2)") (class "Default")
      (node (ref "U13") (pin "2") (pinfunction "2_2") (pintype "unspecified"))
    )
    (net (code "88") (name "unconnected-(U13-Pad3)") (class "Default")
      (node (ref "U13") (pin "3") (pinfunction "3_3") (pintype "unspecified"))
    )
    (net (code "89") (name "unconnected-(U13-Pad4)") (class "Default")
      (node (ref "U13") (pin "4") (pinfunction "4_4") (pintype "unspecified"))
    )
    (net (code "90") (name "unconnected-(U13-Pad5)") (class "Default")
      (node (ref "U13") (pin "5") (pinfunction "5_5") (pintype "unspecified"))
    )
    (net (code "91") (name "unconnected-(U13-Pad8)") (class "Default")
      (node (ref "U13") (pin "8") (pinfunction "8_8") (pintype "unspecified"))
    )
    (net (code "92") (name "unconnected-(U13-Pad9)") (class "Default")
      (node (ref "U13") (pin "9") (pinfunction "9_9") (pintype "unspecified"))
    )
    (net (code "93") (name "unconnected-(U13-Pad10)") (class "Default")
      (node (ref "U13") (pin "10") (pinfunction "10_10") (pintype "unspecified"))
    )
    (net (code "94") (name "unconnected-(U13-Pad11)") (class "Default")
      (node (ref "U13") (pin "11") (pinfunction "11_11") (pintype "unspecified"))
    )
    (net (code "95") (name "unconnected-(U13-Pad12)") (class "Default")
      (node (ref "U13") (pin "12") (pinfunction "12_12") (pintype "unspecified"))
    )
    (net (code "96") (name "unconnected-(U13-Pad13)") (class "Default")
      (node (ref "U13") (pin "13") (pinfunction "13_13") (pintype "unspecified"))
    )
    (net (code "97") (name "unconnected-(U13-Pad14)") (class "Default")
      (node (ref "U13") (pin "14") (pinfunction "14_14") (pintype "unspecified"))
    )
    (net (code "98") (name "unconnected-(U13-Pad15)") (class "Default")
      (node (ref "U13") (pin "15") (pinfunction "15_15") (pintype "unspecified"))
    )
    (net (code "99") (name "unconnected-(U13-Pad16)") (class "Default")
      (node (ref "U13") (pin "16") (pinfunction "16_16") (pintype "unspecified"))
    )
    (net (code "100") (name "unconnected-(U13-Pad17)") (class "Default")
      (node (ref "U13") (pin "17") (pinfunction "17_17") (pintype "unspecified"))
    )
    (net (code "101") (name "unconnected-(U13-Pad18)") (class "Default")
      (node (ref "U13") (pin "18") (pinfunction "18_18") (pintype "unspecified"))
    )
    (net (code "102") (name "unconnected-(U13-Pad19)") (class "Default")
      (node (ref "U13") (pin "19") (pinfunction "19_19") (pintype "unspecified"))
    )
    (net (code "103") (name "unconnected-(U13-Pad20)") (class "Default")
      (node (ref "U13") (pin "20") (pinfunction "20_20") (pintype "unspecified"))
    )
  )
)
